# DM1098EMB_Connector.net
KiCad netlist of a schematic drawn in Altium Designer
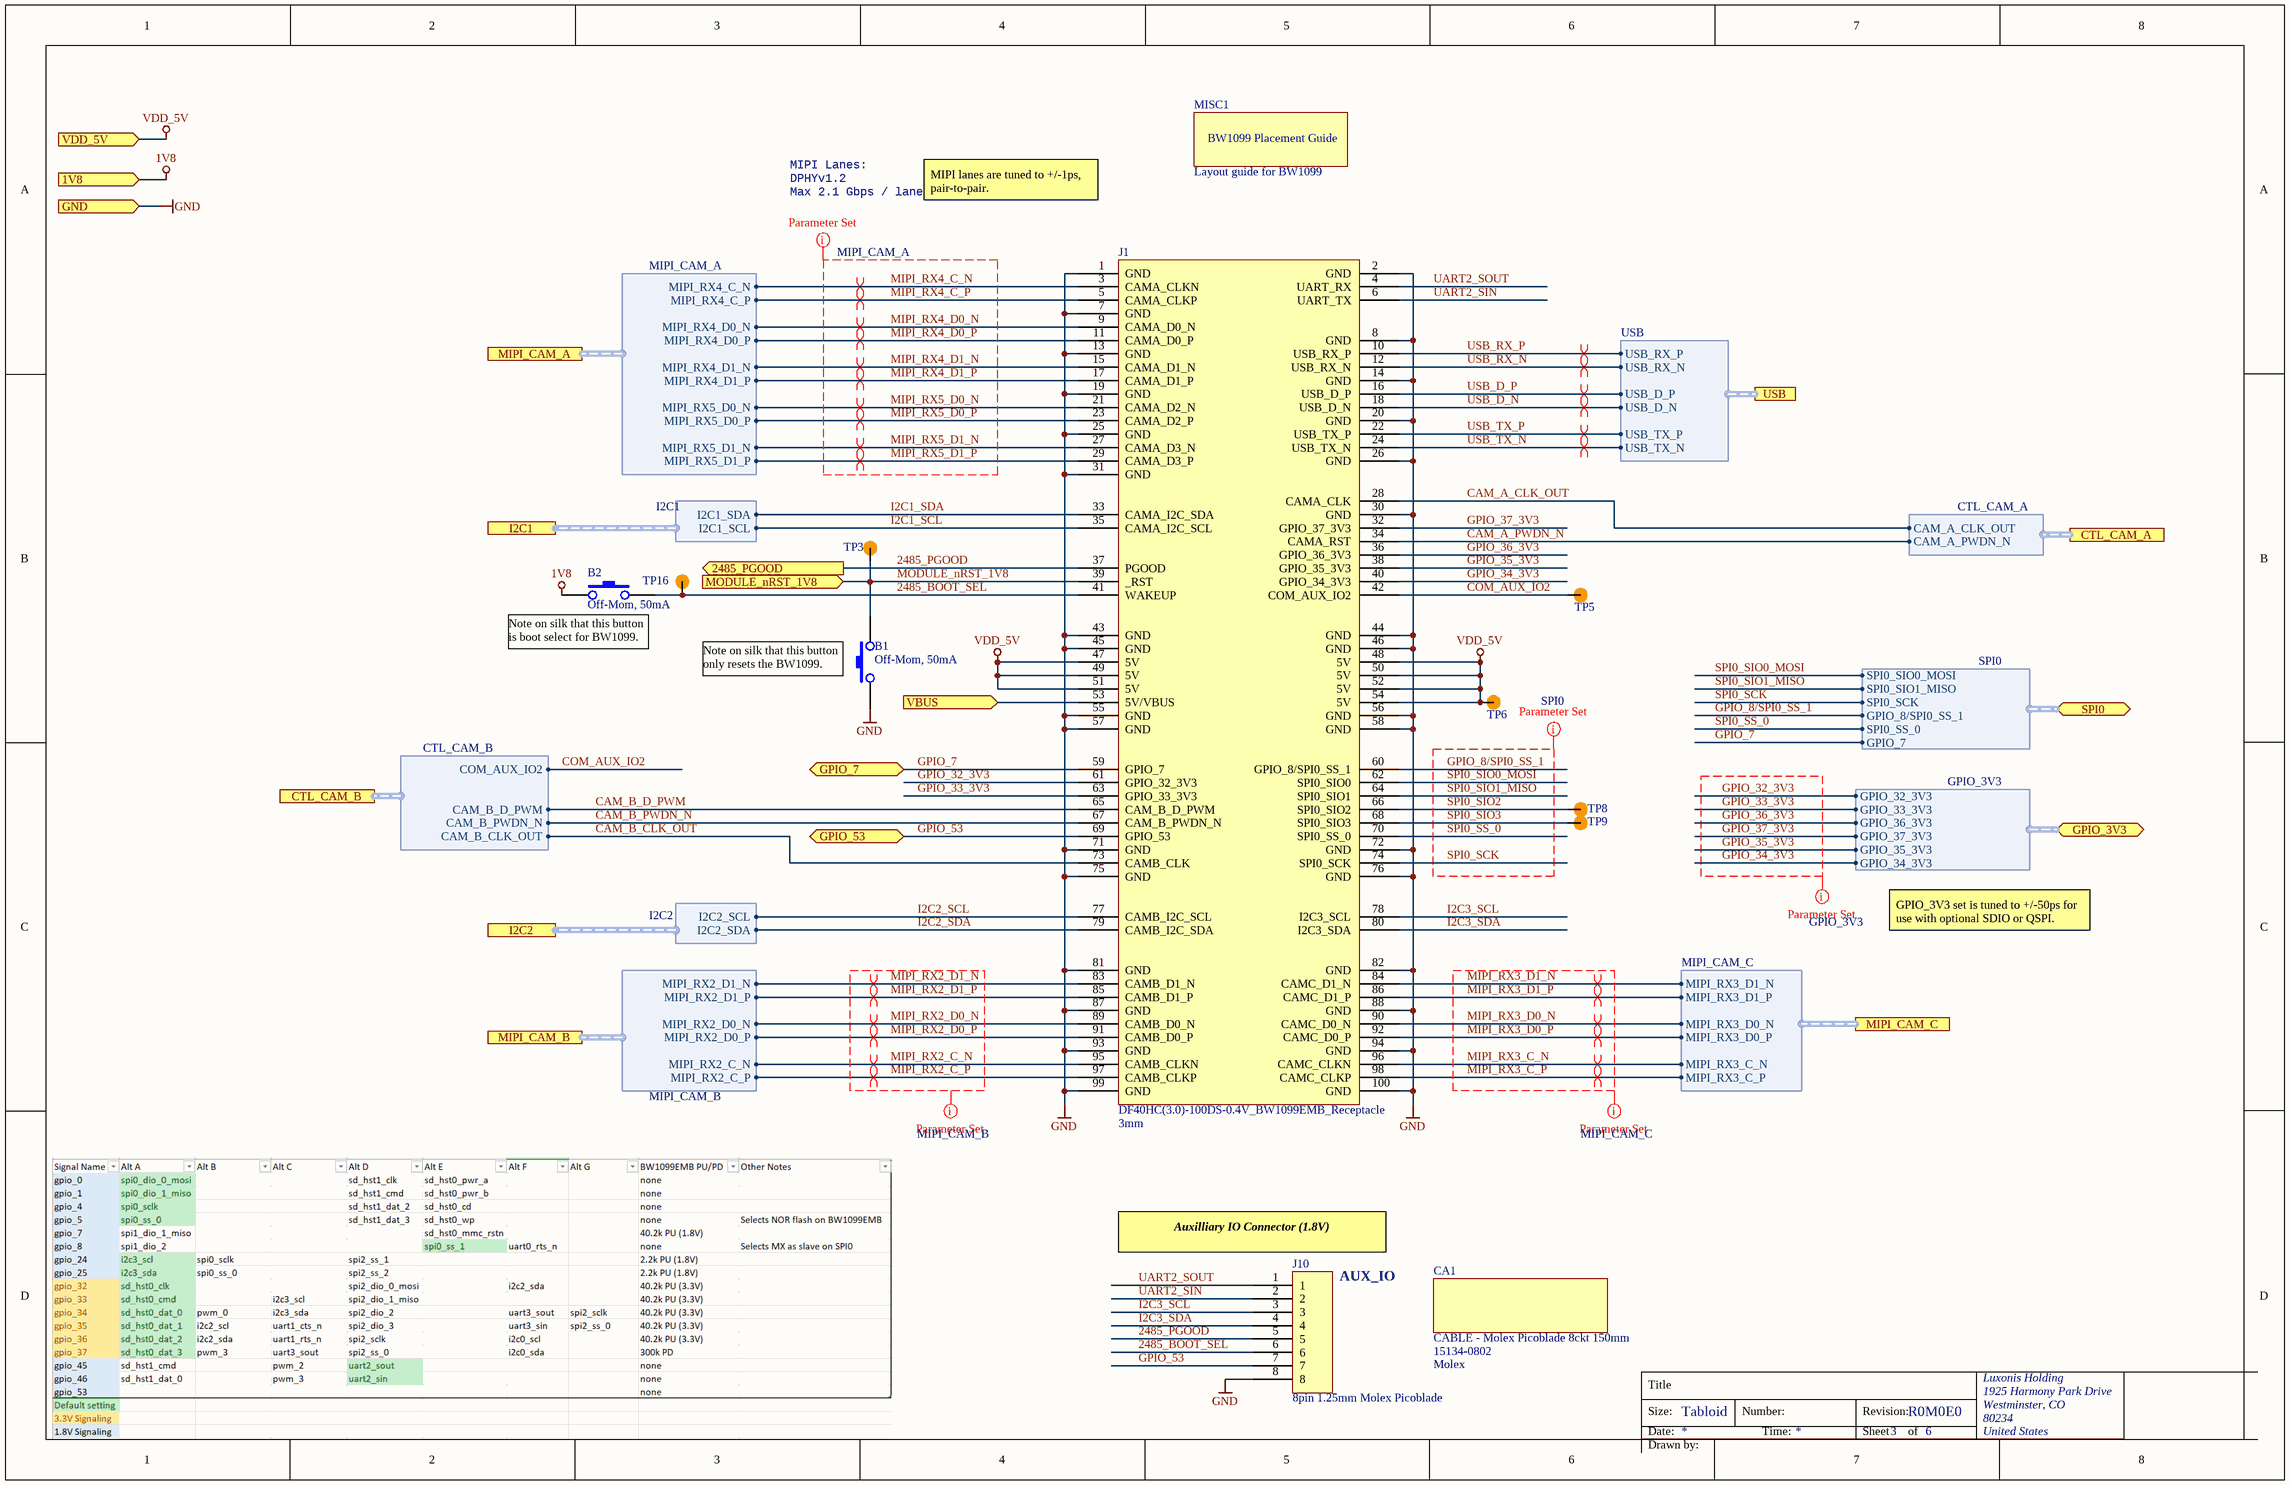
[diagram p0: DM1098EMB_Connector.SchDoc]

(export (version "E")
  (design (tool "Eeschema 10.0.6"))
  (components
    (comp (ref "B1")
      (value "Off-Mom, 50mA")
      (footprint "LuxonisMaster:DTSM-32N-V")
      (description "SWITCH TACTILE SMT 3.5mm * 6mm , brown 160gf")
      (libsource (lib "LuxonisMaster") (part "DTSM-32N-V"))
    )
    (comp (ref "B2")
      (value "Off-Mom, 50mA")
      (footprint "LuxonisMaster:DTSM-32N-V")
      (description "SWITCH TACTILE SMT 3.5mm * 6mm , brown 160gf")
      (libsource (lib "LuxonisMaster") (part "DTSM-32N-V"))
    )
    (comp (ref "CA1")
      (value "CABLE - Molex Picoblade 8ckt 150mm")
      (footprint "LuxonisMaster:15134-0802")
      (description "CABLE ASSY POWER CORD, 8P CRIMP SOCKET, 150MM, BLK")
      (fields
        (field (name "MANUFACTURER PART NUMBER 1") "15134-0802")
        (field (name "MANUFACTURER 1") "Molex")
      )
      (libsource (lib "LuxonisMaster") (part "15134-0802"))
    )
    (comp (ref "J1")
      (value "DF40HC(3.0)-100DS-0.4V_BW1099EMB_Receptacle")
      (footprint "LuxonisMaster:DF40HC-3.0-100DS-0.4V_minpad")
      (description "CONN RCPT 100POS 0.4MM SMD GOLD EMB PINOUT")
      (fields (field (name "MATED STACKING HEIGHT") "3mm"))
      (libsource (lib "BW1098EMB_R0M0E0") (part "DF40HC(3.0)-100DS-0.4V_BW1099EMB"))
    )
    (comp (ref "J10")
      (value "8pin 1.25mm Molex Picoblade")
      (footprint "LuxonisMaster:53047-0810")
      (description "CONN HEADER VERT 8POS 1.25MM  Connector Header Through Hole 8 position 0.049\" (1.25mm)")
      (libsource (lib "LuxonisMaster") (part "53047-0810"))
    )
    (comp (ref "MISC1")
      (value "Layout guide for BW1099")
      (footprint "BW1099_R3_KTHSNF_Footprint")
      (description "MISC - Use for aligning BW1099 mount")
      (libsource (lib "LuxonisMaster") (part "BW1099_Footprint"))
    )
    (comp (ref "TP3")
      (value "TP100_200_NS")
      (footprint "LuxonisMaster:TP100_200_NS")
      (libsource (lib "LuxonisMaster") (part "TEST_POINT"))
    )
    (comp (ref "TP5")
      (value "TP100_200_NS")
      (footprint "LuxonisMaster:TP100_200_NS")
      (libsource (lib "LuxonisMaster") (part "TEST_POINT"))
    )
    (comp (ref "TP6")
      (value "TP100_200_NS")
      (footprint "LuxonisMaster:TP100_200_NS")
      (libsource (lib "LuxonisMaster") (part "TEST_POINT"))
    )
    (comp (ref "TP8")
      (value "TP100_200_NS")
      (footprint "LuxonisMaster:TP100_200_NS")
      (libsource (lib "LuxonisMaster") (part "TEST_POINT"))
    )
    (comp (ref "TP9")
      (value "TP100_200_NS")
      (footprint "LuxonisMaster:TP100_200_NS")
      (libsource (lib "LuxonisMaster") (part "TEST_POINT"))
    )
    (comp (ref "TP16")
      (value "TP100_200_NS")
      (footprint "LuxonisMaster:TP100_200_NS")
      (libsource (lib "LuxonisMaster") (part "TEST_POINT"))
    )
  )
  (nets
    (net (code "11") (name "/2485_BOOT_SEL") (class "Default")
      (node (ref "B2") (pin "2") (pinfunction "2_2") (pintype "passive"))
      (node (ref "J1") (pin "41") (pinfunction "WAKEUP_41") (pintype "passive"))
      (node (ref "J10") (pin "6") (pinfunction "6_6") (pintype "passive"))
      (node (ref "TP16") (pin "1") (pintype "passive"))
    )
    (net (code "12") (name "/2485_PGOOD") (class "Default")
      (node (ref "J1") (pin "37") (pinfunction "PGOOD_37") (pintype "passive"))
      (node (ref "J10") (pin "5") (pinfunction "5_5") (pintype "passive"))
    )
    (net (code "13") (name "/CAM_A_CLK_OUT") (class "Default")
      (node (ref "J1") (pin "28") (pinfunction "CAMA_CLK_28") (pintype "passive"))
    )
    (net (code "14") (name "/CAM_A_PWDN_N") (class "Default")
      (node (ref "J1") (pin "34") (pinfunction "CAMA_RST_34") (pintype "passive"))
    )
    (net (code "15") (name "/CAM_B_CLK_OUT") (class "Default")
      (node (ref "J1") (pin "73") (pinfunction "CAMB_CLK_73") (pintype "passive"))
    )
    (net (code "16") (name "/CAM_B_D_PWM") (class "Default")
      (node (ref "J1") (pin "65") (pinfunction "CAM_B_D_PWM_65") (pintype "passive"))
    )
    (net (code "17") (name "/CAM_B_PWDN_N") (class "Default")
      (node (ref "J1") (pin "67") (pinfunction "CAM_B_PWDN_N_67") (pintype "passive"))
    )
    (net (code "18") (name "/COM_AUX_IO2") (class "Default")
      (node (ref "J1") (pin "42") (pinfunction "COM_AUX_IO2_42") (pintype "passive"))
      (node (ref "TP5") (pin "1") (pintype "passive"))
    )
    (net (code "19") (name "/GPIO_7") (class "Default")
      (node (ref "J1") (pin "59") (pinfunction "GPIO_7_59") (pintype "passive"))
    )
    (net (code "20") (name "/GPIO_8{slash}SPI0_SS_1") (class "Default")
      (node (ref "J1") (pin "60") (pinfunction "GPIO_8/SPI0_SS_1_60") (pintype "passive"))
    )
    (net (code "21") (name "/GPIO_32_3V3") (class "Default")
      (node (ref "J1") (pin "61") (pinfunction "GPIO_32_3V3_61") (pintype "passive"))
    )
    (net (code "22") (name "/GPIO_33_3V3") (class "Default")
      (node (ref "J1") (pin "63") (pinfunction "GPIO_33_3V3_63") (pintype "passive"))
    )
    (net (code "23") (name "/GPIO_34_3V3") (class "Default")
      (node (ref "J1") (pin "40") (pinfunction "GPIO_34_3V3_40") (pintype "passive"))
    )
    (net (code "24") (name "/GPIO_35_3V3") (class "Default")
      (node (ref "J1") (pin "38") (pinfunction "GPIO_35_3V3_38") (pintype "passive"))
    )
    (net (code "25") (name "/GPIO_36_3V3") (class "Default")
      (node (ref "J1") (pin "36") (pinfunction "GPIO_36_3V3_36") (pintype "passive"))
    )
    (net (code "26") (name "/GPIO_37_3V3") (class "Default")
      (node (ref "J1") (pin "32") (pinfunction "GPIO_37_3V3_32") (pintype "passive"))
    )
    (net (code "27") (name "/GPIO_53") (class "Default")
      (node (ref "J1") (pin "69") (pinfunction "GPIO_53_69") (pintype "passive"))
      (node (ref "J10") (pin "7") (pinfunction "7_7") (pintype "passive"))
    )
    (net (code "28") (name "/I2C1_SCL") (class "Default")
      (node (ref "J1") (pin "35") (pinfunction "CAMA_I2C_SCL_35") (pintype "passive"))
    )
    (net (code "29") (name "/I2C1_SDA") (class "Default")
      (node (ref "J1") (pin "33") (pinfunction "CAMA_I2C_SDA_33") (pintype "passive"))
    )
    (net (code "30") (name "/I2C2_SCL") (class "Default")
      (node (ref "J1") (pin "77") (pinfunction "CAMB_I2C_SCL_77") (pintype "passive"))
    )
    (net (code "31") (name "/I2C2_SDA") (class "Default")
      (node (ref "J1") (pin "79") (pinfunction "CAMB_I2C_SDA_79") (pintype "passive"))
    )
    (net (code "32") (name "/I2C3_SCL") (class "Default")
      (node (ref "J1") (pin "78") (pinfunction "I2C3_SCL_78") (pintype "passive"))
      (node (ref "J10") (pin "3") (pinfunction "3_3") (pintype "passive"))
    )
    (net (code "33") (name "/I2C3_SDA") (class "Default")
      (node (ref "J1") (pin "80") (pinfunction "I2C3_SDA_80") (pintype "passive"))
      (node (ref "J10") (pin "4") (pinfunction "4_4") (pintype "passive"))
    )
    (net (code "34") (name "/MIPI_RX2_C_N") (class "Default")
      (node (ref "J1") (pin "95") (pinfunction "CAMB_CLKN_95") (pintype "passive"))
    )
    (net (code "35") (name "/MIPI_RX2_C_P") (class "Default")
      (node (ref "J1") (pin "97") (pinfunction "CAMB_CLKP_97") (pintype "passive"))
    )
    (net (code "36") (name "/MIPI_RX2_D0_N") (class "Default")
      (node (ref "J1") (pin "89") (pinfunction "CAMB_D0_N_89") (pintype "passive"))
    )
    (net (code "37") (name "/MIPI_RX2_D0_P") (class "Default")
      (node (ref "J1") (pin "91") (pinfunction "CAMB_D0_P_91") (pintype "passive"))
    )
    (net (code "38") (name "/MIPI_RX2_D1_N") (class "Default")
      (node (ref "J1") (pin "83") (pinfunction "CAMB_D1_N_83") (pintype "passive"))
    )
    (net (code "39") (name "/MIPI_RX2_D1_P") (class "Default")
      (node (ref "J1") (pin "85") (pinfunction "CAMB_D1_P_85") (pintype "passive"))
    )
    (net (code "40") (name "/MIPI_RX3_C_N") (class "Default")
      (node (ref "J1") (pin "96") (pinfunction "CAMC_CLKN_96") (pintype "passive"))
    )
    (net (code "41") (name "/MIPI_RX3_C_P") (class "Default")
      (node (ref "J1") (pin "98") (pinfunction "CAMC_CLKP_98") (pintype "passive"))
    )
    (net (code "42") (name "/MIPI_RX3_D0_N") (class "Default")
      (node (ref "J1") (pin "90") (pinfunction "CAMC_D0_N_90") (pintype "passive"))
    )
    (net (code "43") (name "/MIPI_RX3_D0_P") (class "Default")
      (node (ref "J1") (pin "92") (pinfunction "CAMC_D0_P_92") (pintype "passive"))
    )
    (net (code "44") (name "/MIPI_RX3_D1_N") (class "Default")
      (node (ref "J1") (pin "84") (pinfunction "CAMC_D1_N_84") (pintype "passive"))
    )
    (net (code "45") (name "/MIPI_RX3_D1_P") (class "Default")
      (node (ref "J1") (pin "86") (pinfunction "CAMC_D1_P_86") (pintype "passive"))
    )
    (net (code "46") (name "/MIPI_RX4_C_N") (class "Default")
      (node (ref "J1") (pin "3") (pinfunction "CAMA_CLKN_3") (pintype "passive"))
    )
    (net (code "47") (name "/MIPI_RX4_C_P") (class "Default")
      (node (ref "J1") (pin "5") (pinfunction "CAMA_CLKP_5") (pintype "passive"))
    )
    (net (code "48") (name "/MIPI_RX4_D0_N") (class "Default")
      (node (ref "J1") (pin "9") (pinfunction "CAMA_D0_N_9") (pintype "passive"))
    )
    (net (code "49") (name "/MIPI_RX4_D0_P") (class "Default")
      (node (ref "J1") (pin "11") (pinfunction "CAMA_D0_P_11") (pintype "passive"))
    )
    (net (code "50") (name "/MIPI_RX4_D1_N") (class "Default")
      (node (ref "J1") (pin "15") (pinfunction "CAMA_D1_N_15") (pintype "passive"))
    )
    (net (code "51") (name "/MIPI_RX4_D1_P") (class "Default")
      (node (ref "J1") (pin "17") (pinfunction "CAMA_D1_P_17") (pintype "passive"))
    )
    (net (code "52") (name "/MIPI_RX5_D0_N") (class "Default")
      (node (ref "J1") (pin "21") (pinfunction "CAMA_D2_N_21") (pintype "passive"))
    )
    (net (code "53") (name "/MIPI_RX5_D0_P") (class "Default")
      (node (ref "J1") (pin "23") (pinfunction "CAMA_D2_P_23") (pintype "passive"))
    )
    (net (code "54") (name "/MIPI_RX5_D1_N") (class "Default")
      (node (ref "J1") (pin "27") (pinfunction "CAMA_D3_N_27") (pintype "passive"))
    )
    (net (code "55") (name "/MIPI_RX5_D1_P") (class "Default")
      (node (ref "J1") (pin "29") (pinfunction "CAMA_D3_P_29") (pintype "passive"))
    )
    (net (code "56") (name "/MODULE_nRST_1V8") (class "Default")
      (node (ref "B1") (pin "2") (pinfunction "2_2") (pintype "passive"))
      (node (ref "J1") (pin "39") (pinfunction "_RST_39") (pintype "passive"))
      (node (ref "TP3") (pin "1") (pintype "passive"))
    )
    (net (code "57") (name "/SPI0_SCK") (class "Default")
      (node (ref "J1") (pin "74") (pinfunction "SPI0_SCK_74") (pintype "passive"))
    )
    (net (code "58") (name "/SPI0_SIO0_MOSI") (class "Default")
      (node (ref "J1") (pin "62") (pinfunction "SPI0_SIO0_62") (pintype "passive"))
    )
    (net (code "59") (name "/SPI0_SIO1_MISO") (class "Default")
      (node (ref "J1") (pin "64") (pinfunction "SPI0_SIO1_64") (pintype "passive"))
    )
    (net (code "60") (name "/SPI0_SIO2") (class "Default")
      (node (ref "J1") (pin "66") (pinfunction "SPI0_SIO2_66") (pintype "passive"))
      (node (ref "TP8") (pin "1") (pintype "passive"))
    )
    (net (code "61") (name "/SPI0_SIO3") (class "Default")
      (node (ref "J1") (pin "68") (pinfunction "SPI0_SIO3_68") (pintype "passive"))
      (node (ref "TP9") (pin "1") (pintype "passive"))
    )
    (net (code "62") (name "/SPI0_SS_0") (class "Default")
      (node (ref "J1") (pin "70") (pinfunction "SPI0_SS_0_70") (pintype "passive"))
    )
    (net (code "63") (name "/UART2_SIN") (class "Default")
      (node (ref "J1") (pin "6") (pinfunction "UART_TX_6") (pintype "passive"))
      (node (ref "J10") (pin "2") (pinfunction "2_2") (pintype "passive"))
    )
    (net (code "64") (name "/UART2_SOUT") (class "Default")
      (node (ref "J1") (pin "4") (pinfunction "UART_RX_4") (pintype "passive"))
      (node (ref "J10") (pin "1") (pinfunction "1_1") (pintype "passive"))
    )
    (net (code "65") (name "/USB_D_N") (class "Default")
      (node (ref "J1") (pin "18") (pinfunction "USB_D_N_18") (pintype "passive"))
    )
    (net (code "66") (name "/USB_D_P") (class "Default")
      (node (ref "J1") (pin "16") (pinfunction "USB_D_P_16") (pintype "passive"))
    )
    (net (code "67") (name "/USB_RX_N") (class "Default")
      (node (ref "J1") (pin "12") (pinfunction "USB_RX_N_12") (pintype "passive"))
    )
    (net (code "68") (name "/USB_RX_P") (class "Default")
      (node (ref "J1") (pin "10") (pinfunction "USB_RX_P_10") (pintype "passive"))
    )
    (net (code "69") (name "/USB_TX_N") (class "Default")
      (node (ref "J1") (pin "24") (pinfunction "USB_TX_N_24") (pintype "passive"))
    )
    (net (code "70") (name "/USB_TX_P") (class "Default")
      (node (ref "J1") (pin "22") (pinfunction "USB_TX_P_22") (pintype "passive"))
    )
    (net (code "71") (name "/VBUS") (class "Default")
      (node (ref "J1") (pin "53") (pinfunction "5V/VBUS_53") (pintype "passive"))
    )
    (net (code "82") (name "1V8") (class "Default")
      (node (ref "B2") (pin "1") (pinfunction "1_1") (pintype "passive"))
    )
    (net (code "83") (name "GND") (class "Default")
      (node (ref "B1") (pin "1") (pinfunction "1_1") (pintype "passive"))
      (node (ref "J1") (pin "1") (pinfunction "GND_1") (pintype "passive"))
      (node (ref "J1") (pin "100") (pinfunction "GND_100") (pintype "passive"))
      (node (ref "J1") (pin "13") (pinfunction "GND_13") (pintype "passive"))
      (node (ref "J1") (pin "14") (pinfunction "GND_14") (pintype "passive"))
      (node (ref "J1") (pin "19") (pinfunction "GND_19") (pintype "passive"))
      (node (ref "J1") (pin "2") (pinfunction "GND_2") (pintype "passive"))
      (node (ref "J1") (pin "20") (pinfunction "GND_20") (pintype "passive"))
      (node (ref "J1") (pin "25") (pinfunction "GND_25") (pintype "passive"))
      (node (ref "J1") (pin "26") (pinfunction "GND_26") (pintype "passive"))
      (node (ref "J1") (pin "30") (pinfunction "GND_30") (pintype "passive"))
      (node (ref "J1") (pin "31") (pinfunction "GND_31") (pintype "passive"))
      (node (ref "J1") (pin "43") (pinfunction "GND_43") (pintype "passive"))
      (node (ref "J1") (pin "44") (pinfunction "GND_44") (pintype "passive"))
      (node (ref "J1") (pin "45") (pinfunction "GND_45") (pintype "passive"))
      (node (ref "J1") (pin "46") (pinfunction "GND_46") (pintype "passive"))
      (node (ref "J1") (pin "55") (pinfunction "GND_55") (pintype "passive"))
      (node (ref "J1") (pin "56") (pinfunction "GND_56") (pintype "passive"))
      (node (ref "J1") (pin "57") (pinfunction "GND_57") (pintype "passive"))
      (node (ref "J1") (pin "58") (pinfunction "GND_58") (pintype "passive"))
      (node (ref "J1") (pin "7") (pinfunction "GND_7") (pintype "passive"))
      (node (ref "J1") (pin "71") (pinfunction "GND_71") (pintype "passive"))
      (node (ref "J1") (pin "72") (pinfunction "GND_72") (pintype "passive"))
      (node (ref "J1") (pin "75") (pinfunction "GND_75") (pintype "passive"))
      (node (ref "J1") (pin "76") (pinfunction "GND_76") (pintype "passive"))
      (node (ref "J1") (pin "8") (pinfunction "GND_8") (pintype "passive"))
      (node (ref "J1") (pin "81") (pinfunction "GND_81") (pintype "passive"))
      (node (ref "J1") (pin "82") (pinfunction "GND_82") (pintype "passive"))
      (node (ref "J1") (pin "87") (pinfunction "GND_87") (pintype "passive"))
      (node (ref "J1") (pin "88") (pinfunction "GND_88") (pintype "passive"))
      (node (ref "J1") (pin "93") (pinfunction "GND_93") (pintype "passive"))
      (node (ref "J1") (pin "94") (pinfunction "GND_94") (pintype "passive"))
      (node (ref "J1") (pin "99") (pinfunction "GND_99") (pintype "passive"))
      (node (ref "J10") (pin "8") (pinfunction "8_8") (pintype "passive"))
    )
    (net (code "84") (name "VDD_5V") (class "Default")
      (node (ref "J1") (pin "47") (pinfunction "5V_47") (pintype "passive"))
      (node (ref "J1") (pin "48") (pinfunction "5V_48") (pintype "passive"))
      (node (ref "J1") (pin "49") (pinfunction "5V_49") (pintype "passive"))
      (node (ref "J1") (pin "50") (pinfunction "5V_50") (pintype "passive"))
      (node (ref "J1") (pin "51") (pinfunction "5V_51") (pintype "passive"))
      (node (ref "J1") (pin "52") (pinfunction "5V_52") (pintype "passive"))
      (node (ref "J1") (pin "54") (pinfunction "5V_54") (pintype "passive"))
      (node (ref "TP6") (pin "1") (pintype "passive"))
    )
  )
)
